# ROLETA2-A1-P02.net
KiCad netlist of a schematic drawn in Altium Designer
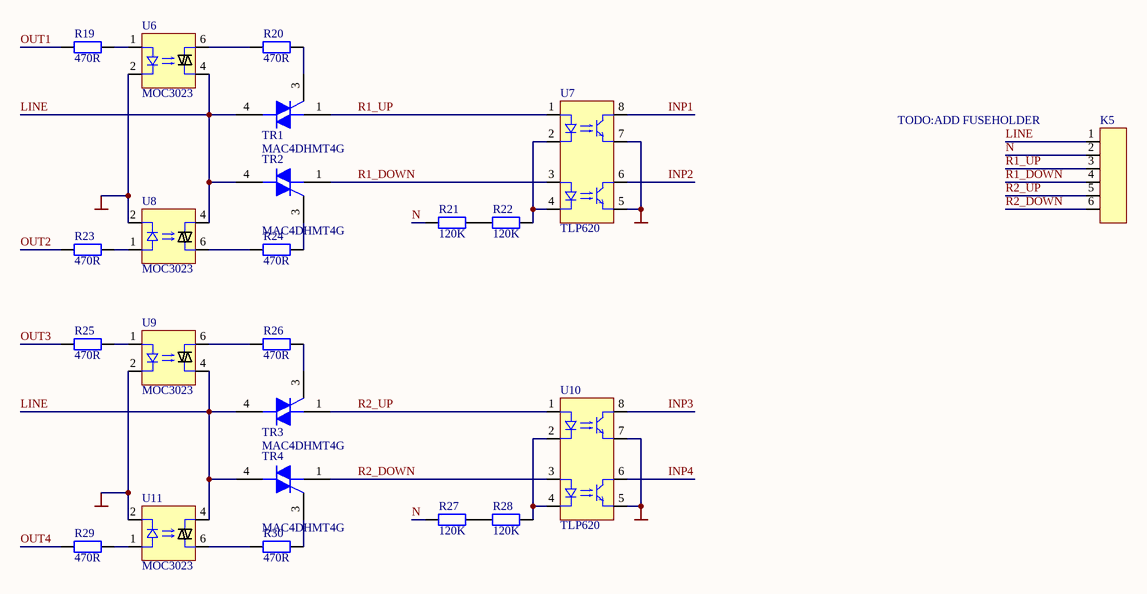
[diagram p0: ROLETA2-A1-P02.SchDoc]

(export (version "E")
  (design (tool "Eeschema 10.0.6"))
  (components
    (comp (ref "K5")
      (value "Terminal Block Connector, 3.81mm, Right Angle")
      (footprint "CONN_3.81_6")
      (description "Terminal Block Connector, 3.81mm, 8pin")
      (libsource (lib "fractal_lib") (part "CONN_TB_3.81_6PIN"))
    )
    (comp (ref "R19")
      (value "470R")
      (footprint "RC0805-1")
      (description "Chip Resistor 0805")
      (libsource (lib "Resistors") (part "RES0805"))
    )
    (comp (ref "R20")
      (value "470R")
      (footprint "RC0805-1")
      (description "Chip Resistor 0805")
      (libsource (lib "Resistors") (part "RES0805"))
    )
    (comp (ref "R21")
      (value "120K")
      (footprint "RC0805-1")
      (description "Chip Resistor 0805")
      (libsource (lib "Resistors") (part "RES0805"))
    )
    (comp (ref "R22")
      (value "120K")
      (footprint "RC0805-1")
      (description "Chip Resistor 0805")
      (libsource (lib "Resistors") (part "RES0805"))
    )
    (comp (ref "R23")
      (value "470R")
      (footprint "RC0805-1")
      (description "Chip Resistor 0805")
      (libsource (lib "Resistors") (part "RES0805"))
    )
    (comp (ref "R24")
      (value "470R")
      (footprint "RC0805-1")
      (description "Chip Resistor 0805")
      (libsource (lib "") (part "RES0805_1"))
    )
    (comp (ref "R25")
      (value "470R")
      (footprint "RC0805-1")
      (description "Chip Resistor 0805")
      (libsource (lib "Resistors") (part "RES0805"))
    )
    (comp (ref "R26")
      (value "470R")
      (footprint "RC0805-1")
      (description "Chip Resistor 0805")
      (libsource (lib "Resistors") (part "RES0805"))
    )
    (comp (ref "R27")
      (value "120K")
      (footprint "RC0805-1")
      (description "Chip Resistor 0805")
      (libsource (lib "Resistors") (part "RES0805"))
    )
    (comp (ref "R28")
      (value "120K")
      (footprint "RC0805-1")
      (description "Chip Resistor 0805")
      (libsource (lib "Resistors") (part "RES0805"))
    )
    (comp (ref "R29")
      (value "470R")
      (footprint "RC0805-1")
      (description "Chip Resistor 0805")
      (libsource (lib "Resistors") (part "RES0805"))
    )
    (comp (ref "R30")
      (value "470R")
      (footprint "RC0805-1")
      (description "Chip Resistor 0805")
      (libsource (lib "") (part "RES0805_1"))
    )
    (comp (ref "TR1")
      (value "MAC4DHMT4G")
      (footprint "ONSC-DPAK-3-369C-01_V")
      (description "Sensitive Gate Triacs, 3-Pin DPAK, Pb-Free, Tape and Reel")
      (fields (field (name "MANUFACTURER") "On Semiconductor"))
      (libsource (lib "fractal_lib") (part "MAC4DHMT4G"))
    )
    (comp (ref "TR2")
      (value "MAC4DHMT4G")
      (footprint "ONSC-DPAK-3-369C-01_V")
      (description "Sensitive Gate Triacs, 3-Pin DPAK, Pb-Free, Tape and Reel")
      (fields (field (name "MANUFACTURER") "On Semiconductor"))
      (libsource (lib "fractal_lib") (part "MAC4DHMT4G"))
    )
    (comp (ref "TR3")
      (value "MAC4DHMT4G")
      (footprint "ONSC-DPAK-3-369C-01_V")
      (description "Sensitive Gate Triacs, 3-Pin DPAK, Pb-Free, Tape and Reel")
      (fields (field (name "MANUFACTURER") "On Semiconductor"))
      (libsource (lib "fractal_lib") (part "MAC4DHMT4G"))
    )
    (comp (ref "TR4")
      (value "MAC4DHMT4G")
      (footprint "ONSC-DPAK-3-369C-01_V")
      (description "Sensitive Gate Triacs, 3-Pin DPAK, Pb-Free, Tape and Reel")
      (fields (field (name "MANUFACTURER") "On Semiconductor"))
      (libsource (lib "fractal_lib") (part "MAC4DHMT4G"))
    )
    (comp (ref "U6")
      (value "MOC3023")
      (footprint "DIP6")
      (description "digital temperature sensor")
      (libsource (lib "fractal_lib") (part "MOC3023"))
    )
    (comp (ref "U7")
      (value "TLP620")
      (footprint "DIP8")
      (description "digital temperature sensor")
      (libsource (lib "fractal_lib") (part "TLP620"))
    )
    (comp (ref "U8")
      (value "MOC3023")
      (footprint "DIP6")
      (description "digital temperature sensor")
      (libsource (lib "") (part "MOC3023_1"))
    )
    (comp (ref "U9")
      (value "MOC3023")
      (footprint "DIP6")
      (description "digital temperature sensor")
      (libsource (lib "fractal_lib") (part "MOC3023"))
    )
    (comp (ref "U10")
      (value "TLP620")
      (footprint "DIP8")
      (description "digital temperature sensor")
      (libsource (lib "fractal_lib") (part "TLP620"))
    )
    (comp (ref "U11")
      (value "MOC3023")
      (footprint "DIP6")
      (description "digital temperature sensor")
      (libsource (lib "") (part "MOC3023_1"))
    )
  )
  (nets
    (net (code "1") (name "/INP1") (class "Default")
      (node (ref "U7") (pin "8") (pinfunction "C_8") (pintype "passive"))
    )
    (net (code "2") (name "/INP2") (class "Default")
      (node (ref "U7") (pin "6") (pinfunction "C_6") (pintype "passive"))
    )
    (net (code "3") (name "/INP3") (class "Default")
      (node (ref "U10") (pin "8") (pinfunction "C_8") (pintype "passive"))
    )
    (net (code "4") (name "/INP4") (class "Default")
      (node (ref "U10") (pin "6") (pinfunction "C_6") (pintype "passive"))
    )
    (net (code "5") (name "/LINE") (class "Default")
      (node (ref "K5") (pin "1") (pinfunction "A_1") (pintype "passive"))
      (node (ref "TR1") (pin "4") (pinfunction "MT2_4") (pintype "passive"))
      (node (ref "TR2") (pin "4") (pinfunction "MT2_4") (pintype "passive"))
      (node (ref "TR3") (pin "4") (pinfunction "MT2_4") (pintype "passive"))
      (node (ref "TR4") (pin "4") (pinfunction "MT2_4") (pintype "passive"))
      (node (ref "U11") (pin "4") (pinfunction "E_4") (pintype "passive"))
      (node (ref "U6") (pin "4") (pinfunction "E_4") (pintype "passive"))
      (node (ref "U8") (pin "4") (pinfunction "E_4") (pintype "passive"))
      (node (ref "U9") (pin "4") (pinfunction "E_4") (pintype "passive"))
    )
    (net (code "6") (name "/N") (class "Default")
      (node (ref "K5") (pin "2") (pinfunction "K_2") (pintype "passive"))
      (node (ref "R21") (pin "2") (pinfunction "2_2") (pintype "passive"))
      (node (ref "R27") (pin "2") (pinfunction "2_2") (pintype "passive"))
    )
    (net (code "7") (name "/OUT1") (class "Default")
      (node (ref "R19") (pin "2") (pinfunction "2_2") (pintype "passive"))
    )
    (net (code "8") (name "/OUT2") (class "Default")
      (node (ref "R23") (pin "2") (pinfunction "2_2") (pintype "passive"))
    )
    (net (code "9") (name "/OUT3") (class "Default")
      (node (ref "R25") (pin "2") (pinfunction "2_2") (pintype "passive"))
    )
    (net (code "10") (name "/OUT4") (class "Default")
      (node (ref "R29") (pin "2") (pinfunction "2_2") (pintype "passive"))
    )
    (net (code "11") (name "/R1_DOWN") (class "Default")
      (node (ref "K5") (pin "4") (pinfunction "K_4") (pintype "passive"))
      (node (ref "TR2") (pin "1") (pinfunction "MT1_1") (pintype "passive"))
      (node (ref "U7") (pin "3") (pinfunction "A_3") (pintype "passive"))
    )
    (net (code "12") (name "/R1_UP") (class "Default")
      (node (ref "K5") (pin "3") (pinfunction "A_3") (pintype "passive"))
      (node (ref "TR1") (pin "1") (pinfunction "MT1_1") (pintype "passive"))
      (node (ref "U7") (pin "1") (pinfunction "A_1") (pintype "passive"))
    )
    (net (code "13") (name "/R2_DOWN") (class "Default")
      (node (ref "K5") (pin "6") (pinfunction "C_6") (pintype "passive"))
      (node (ref "TR4") (pin "1") (pinfunction "MT1_1") (pintype "passive"))
      (node (ref "U10") (pin "3") (pinfunction "A_3") (pintype "passive"))
    )
    (net (code "14") (name "/R2_UP") (class "Default")
      (node (ref "K5") (pin "5") (pinfunction "E_5") (pintype "passive"))
      (node (ref "TR3") (pin "1") (pinfunction "MT1_1") (pintype "passive"))
      (node (ref "U10") (pin "1") (pinfunction "A_1") (pintype "passive"))
    )
    (net (code "15") (name "GND") (class "Default")
      (node (ref "U10") (pin "5") (pinfunction "E_5") (pintype "passive"))
      (node (ref "U10") (pin "7") (pinfunction "E_7") (pintype "passive"))
      (node (ref "U11") (pin "2") (pinfunction "K_2") (pintype "passive"))
      (node (ref "U6") (pin "2") (pinfunction "K_2") (pintype "passive"))
      (node (ref "U7") (pin "5") (pinfunction "E_5") (pintype "passive"))
      (node (ref "U7") (pin "7") (pinfunction "E_7") (pintype "passive"))
      (node (ref "U8") (pin "2") (pinfunction "K_2") (pintype "passive"))
      (node (ref "U9") (pin "2") (pinfunction "K_2") (pintype "passive"))
    )
    (net (code "16") (name "Net-(R21-Pad1)") (class "Default")
      (node (ref "R21") (pin "1") (pinfunction "1_1") (pintype "passive"))
      (node (ref "R22") (pin "2") (pinfunction "2_2") (pintype "passive"))
    )
    (net (code "17") (name "Net-(R22-Pad1)") (class "Default")
      (node (ref "R22") (pin "1") (pinfunction "1_1") (pintype "passive"))
      (node (ref "U7") (pin "2") (pinfunction "K_2") (pintype "passive"))
      (node (ref "U7") (pin "4") (pinfunction "K_4") (pintype "passive"))
    )
    (net (code "18") (name "Net-(R27-Pad1)") (class "Default")
      (node (ref "R27") (pin "1") (pinfunction "1_1") (pintype "passive"))
      (node (ref "R28") (pin "2") (pinfunction "2_2") (pintype "passive"))
    )
    (net (code "19") (name "Net-(R28-Pad1)") (class "Default")
      (node (ref "R28") (pin "1") (pinfunction "1_1") (pintype "passive"))
      (node (ref "U10") (pin "2") (pinfunction "K_2") (pintype "passive"))
      (node (ref "U10") (pin "4") (pinfunction "K_4") (pintype "passive"))
    )
    (net (code "20") (name "Net-(TR1-G)") (class "Default")
      (node (ref "R20") (pin "1") (pinfunction "1_1") (pintype "passive"))
      (node (ref "TR1") (pin "3") (pinfunction "G_3") (pintype "passive"))
    )
    (net (code "21") (name "Net-(TR2-G)") (class "Default")
      (node (ref "R24") (pin "1") (pinfunction "1_1") (pintype "passive"))
      (node (ref "TR2") (pin "3") (pinfunction "G_3") (pintype "passive"))
    )
    (net (code "22") (name "Net-(TR3-G)") (class "Default")
      (node (ref "R26") (pin "1") (pinfunction "1_1") (pintype "passive"))
      (node (ref "TR3") (pin "3") (pinfunction "G_3") (pintype "passive"))
    )
    (net (code "23") (name "Net-(TR4-G)") (class "Default")
      (node (ref "R30") (pin "1") (pinfunction "1_1") (pintype "passive"))
      (node (ref "TR4") (pin "3") (pinfunction "G_3") (pintype "passive"))
    )
    (net (code "24") (name "Net-(U6-A)") (class "Default")
      (node (ref "R19") (pin "1") (pinfunction "1_1") (pintype "passive"))
      (node (ref "U6") (pin "1") (pinfunction "A_1") (pintype "passive"))
    )
    (net (code "25") (name "Net-(U6-C)") (class "Default")
      (node (ref "R20") (pin "2") (pinfunction "2_2") (pintype "passive"))
      (node (ref "U6") (pin "6") (pinfunction "C_6") (pintype "passive"))
    )
    (net (code "26") (name "Net-(U8-A)") (class "Default")
      (node (ref "R23") (pin "1") (pinfunction "1_1") (pintype "passive"))
      (node (ref "U8") (pin "1") (pinfunction "A_1") (pintype "passive"))
    )
    (net (code "27") (name "Net-(U8-C)") (class "Default")
      (node (ref "R24") (pin "2") (pinfunction "2_2") (pintype "passive"))
      (node (ref "U8") (pin "6") (pinfunction "C_6") (pintype "passive"))
    )
    (net (code "28") (name "Net-(U9-A)") (class "Default")
      (node (ref "R25") (pin "1") (pinfunction "1_1") (pintype "passive"))
      (node (ref "U9") (pin "1") (pinfunction "A_1") (pintype "passive"))
    )
    (net (code "29") (name "Net-(U9-C)") (class "Default")
      (node (ref "R26") (pin "2") (pinfunction "2_2") (pintype "passive"))
      (node (ref "U9") (pin "6") (pinfunction "C_6") (pintype "passive"))
    )
    (net (code "30") (name "Net-(U11-A)") (class "Default")
      (node (ref "R29") (pin "1") (pinfunction "1_1") (pintype "passive"))
      (node (ref "U11") (pin "1") (pinfunction "A_1") (pintype "passive"))
    )
    (net (code "31") (name "Net-(U11-C)") (class "Default")
      (node (ref "R30") (pin "2") (pinfunction "2_2") (pintype "passive"))
      (node (ref "U11") (pin "6") (pinfunction "C_6") (pintype "passive"))
    )
  )
)
